# Titan_Balancer.net
KiCad netlist of a schematic drawn in EAGLE
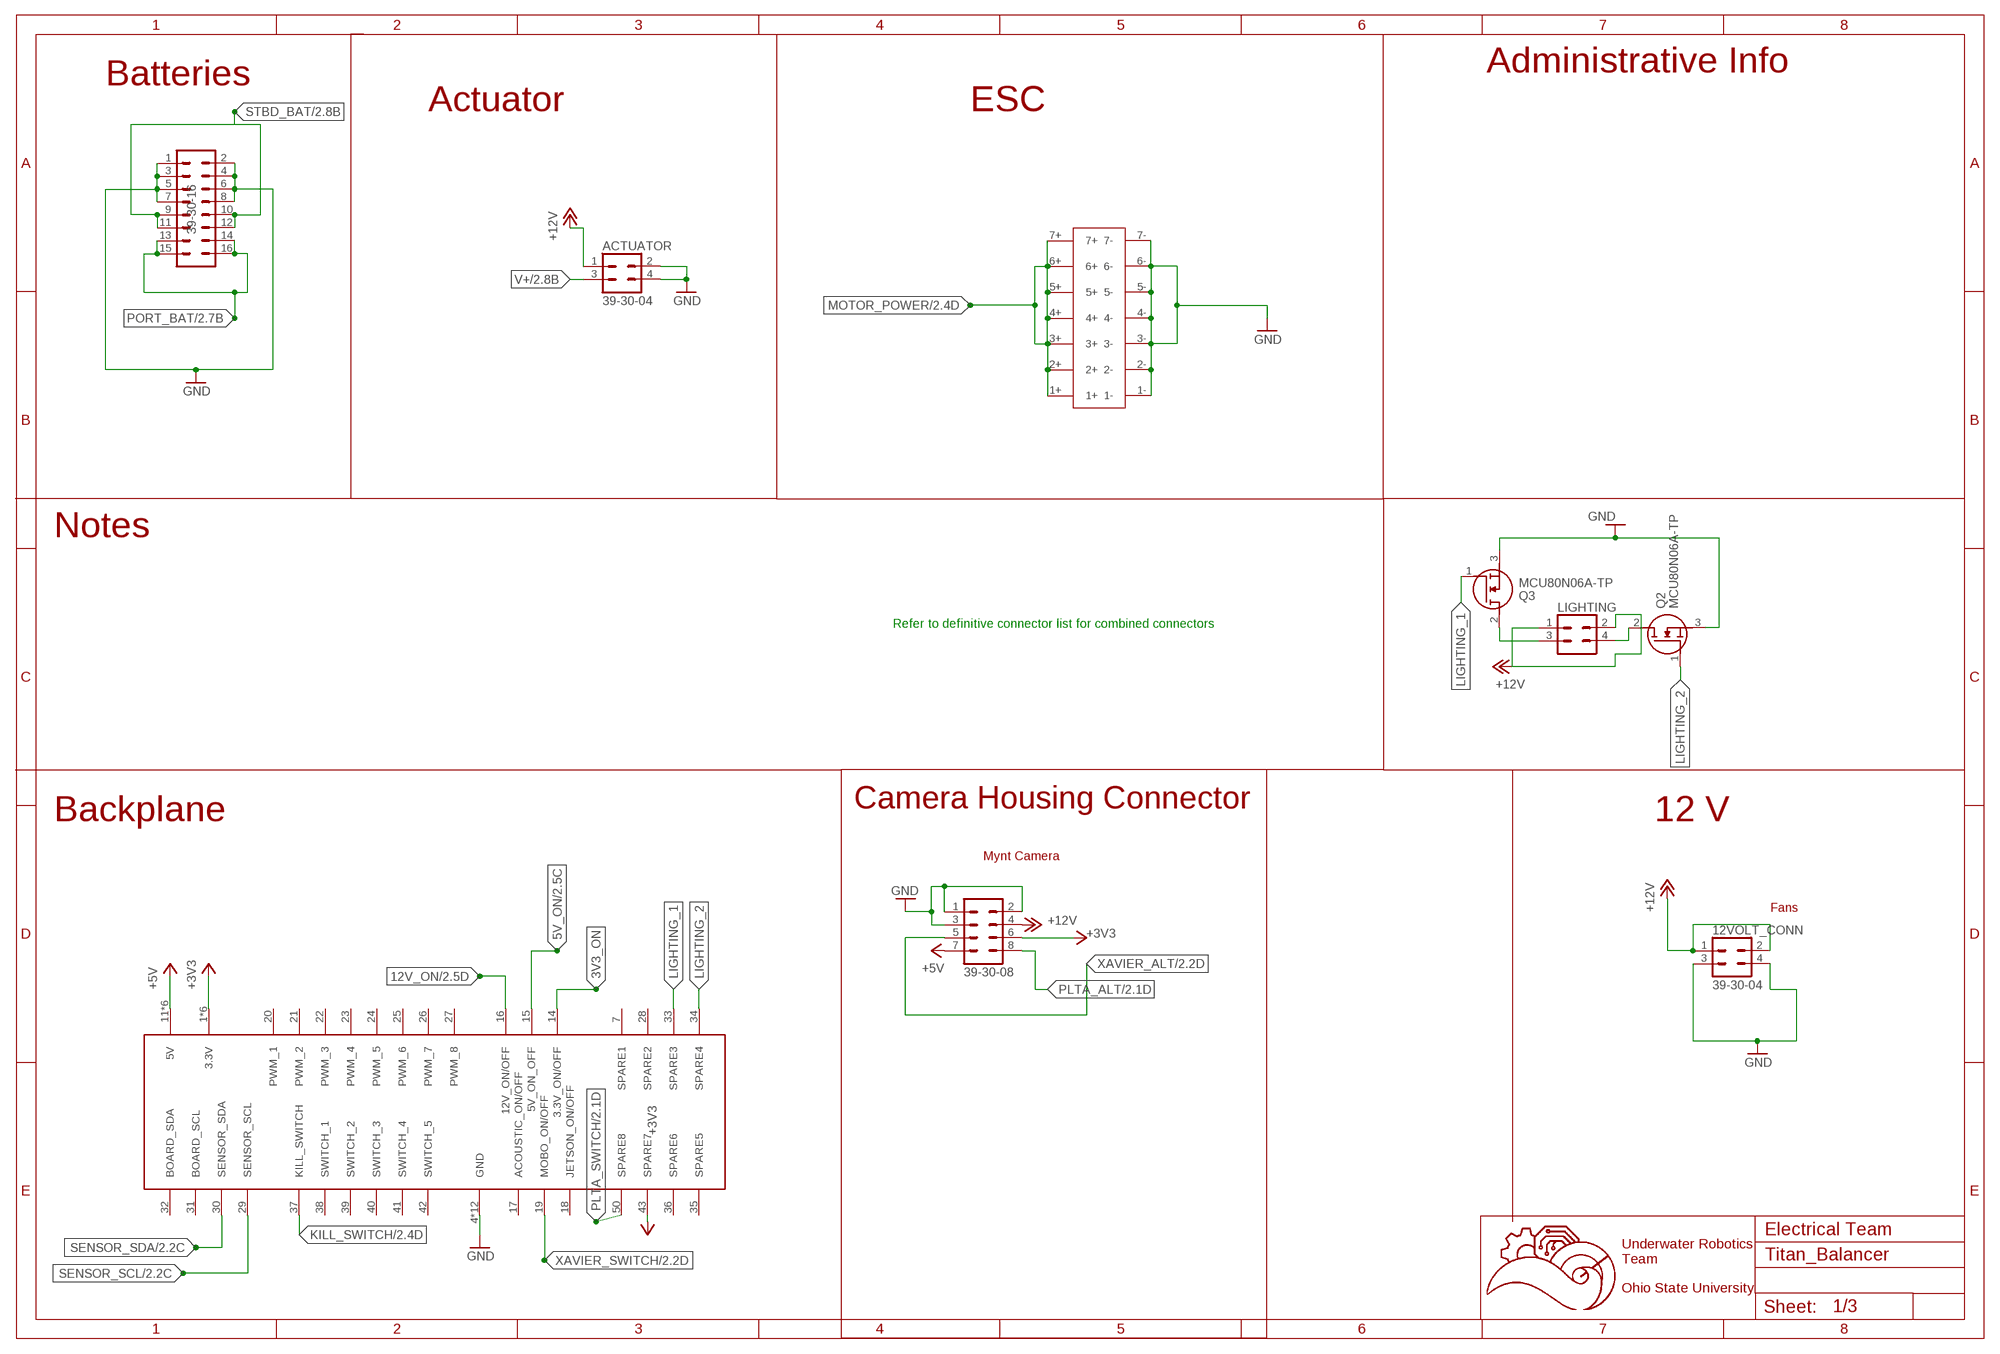
[diagram p0: schematic, sheet 1]
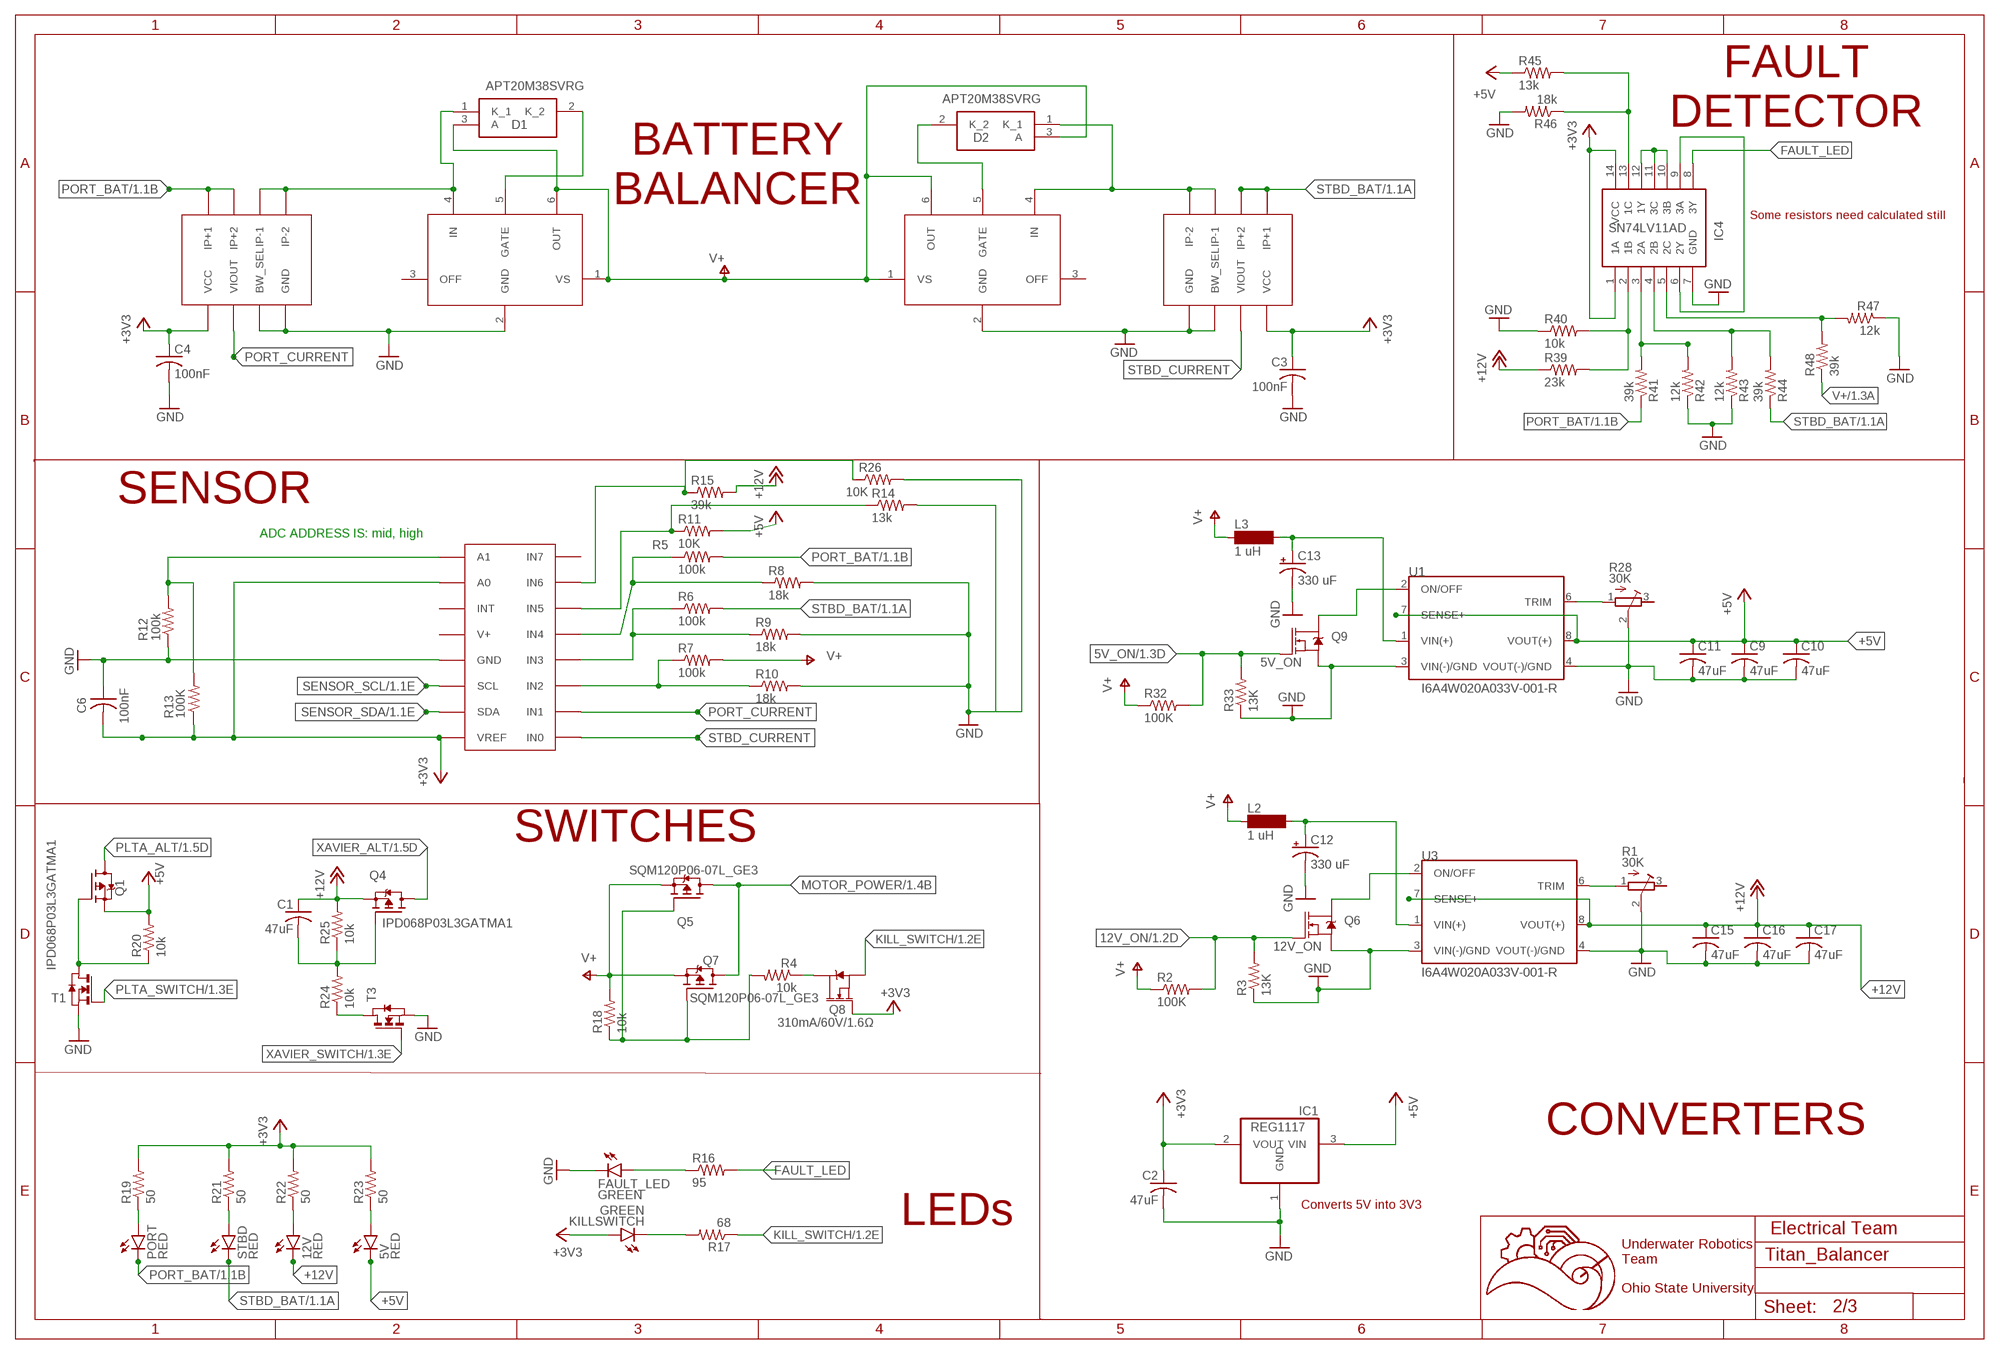
[diagram p1: schematic, sheet 2]
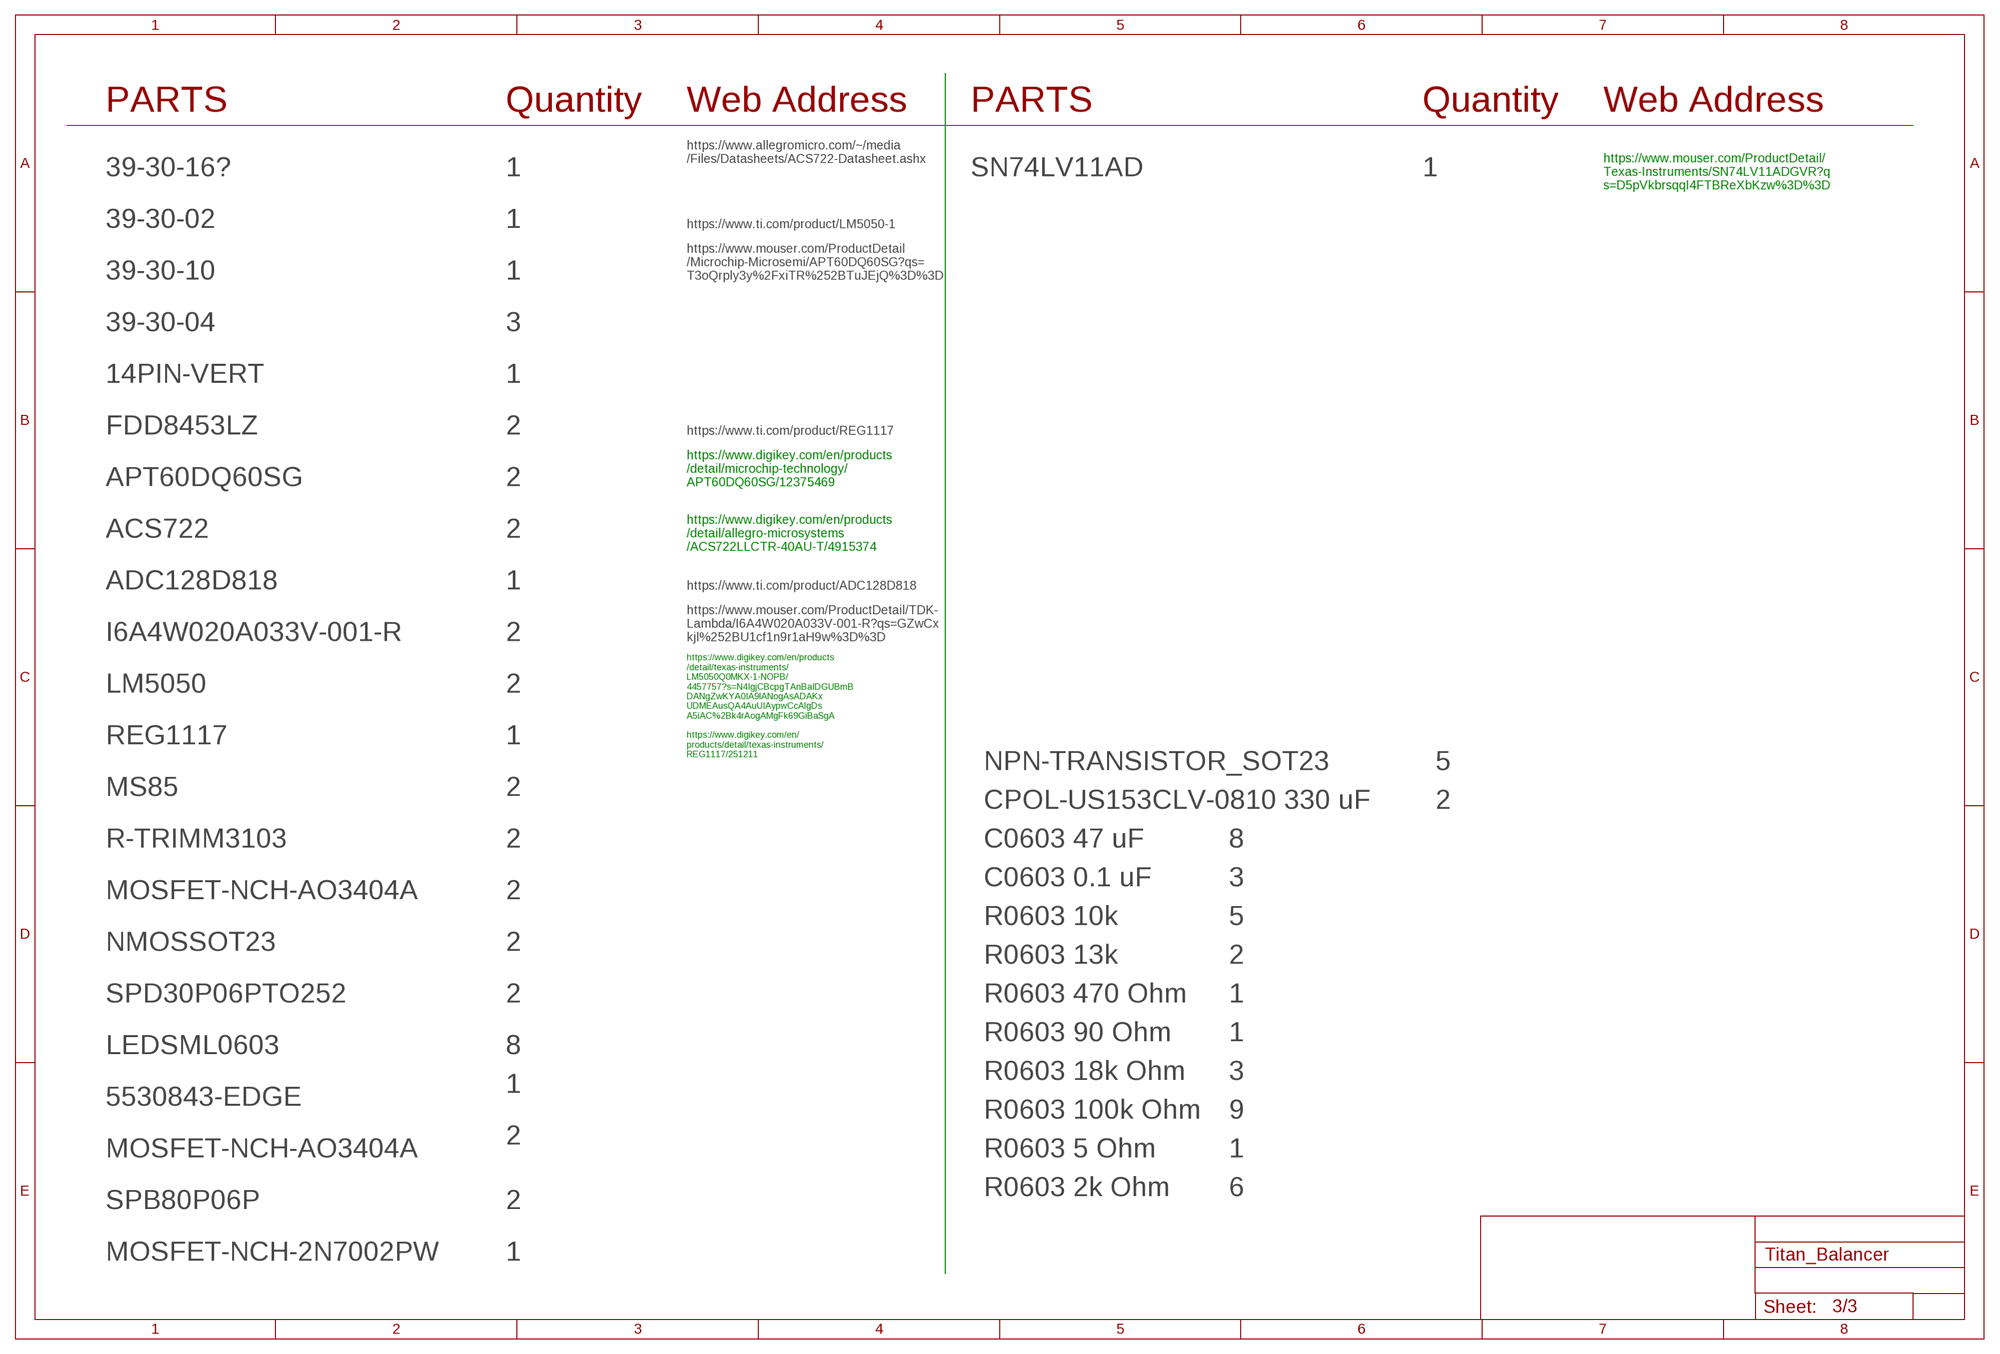
[diagram p2: schematic, sheet 3]

(export (version "E")
  (design (tool "Eeschema 10.0.6"))
  (components
    (comp (ref "12VOLT_CONN")
      (value "39-30-04")
      (footprint "eagle-import:39-30-_04_")
      (libsource (lib "eagle-import") (part "39-30-?04?"))
    )
    (comp (ref "ACTUATOR")
      (value "39-30-04")
      (footprint "eagle-import:39-30-_04_")
      (libsource (lib "eagle-import") (part "39-30-?04?"))
    )
    (comp (ref "BATTERYCONNECTOR")
      (value "39-30-16")
      (footprint "eagle-import:39-30-_16_")
      (libsource (lib "eagle-import") (part "39-30-?16?"))
    )
    (comp (ref "ESC_CONN")
      (value "14PIN-VERT")
      (footprint "eagle-import:14PIN_VERT")
      (libsource (lib "eagle-import") (part "14PIN-VERT"))
    )
    (comp (ref "LIGHTING")
      (value "39-30-04")
      (footprint "eagle-import:39-30-_04_")
      (libsource (lib "eagle-import") (part "39-30-?04?"))
    )
    (comp (ref "MYNT_XAVIER_PLTA")
      (value "39-30-08")
      (footprint "eagle-import:39-30-_08_")
      (libsource (lib "eagle-import") (part "39-30-?08?"))
    )
    (comp (ref "Q2")
      (value "MCU80N06A-TP")
      (footprint "eagle-import:FDD8453LZ")
      (fields
        (field (name "MANUFACTURER_PART_NUMBER") "FDD8453LZ")
        (field (name "MOUSER_PART_NUMBER") "512-FDD8453LZ")
      )
      (libsource (lib "eagle-import") (part "FDD8453LZ"))
    )
    (comp (ref "Q3")
      (value "MCU80N06A-TP")
      (footprint "eagle-import:FDD8453LZ")
      (fields
        (field (name "MANUFACTURER_PART_NUMBER") "FDD8453LZ")
        (field (name "MOUSER_PART_NUMBER") "512-FDD8453LZ")
      )
      (libsource (lib "eagle-import") (part "FDD8453LZ"))
    )
    (comp (ref "U$1")
      (value "5530843-EDGE")
      (footprint "eagle-import:5530843-6-BOARDFINGERS")
      (libsource (lib "eagle-import") (part "5530843-EDGE"))
    )
    (comp (ref "5V")
      (value "RED")
      (footprint "eagle-import:SML0603")
      (libsource (lib "eagle-import") (part "LEDSML0603"))
    )
    (comp (ref "12V")
      (value "RED")
      (footprint "eagle-import:SML0603")
      (libsource (lib "eagle-import") (part "LEDSML0603"))
    )
    (comp (ref "C1")
      (value "47uF")
      (footprint "eagle-import:C0603")
      (libsource (lib "eagle-import") (part "C-USC0603"))
    )
    (comp (ref "C2")
      (value "47uF")
      (footprint "eagle-import:C0603")
      (libsource (lib "eagle-import") (part "C-USC0603"))
    )
    (comp (ref "C3")
      (value "100nF")
      (footprint "eagle-import:C0603")
      (libsource (lib "eagle-import") (part "C-USC0603"))
    )
    (comp (ref "C4")
      (value "100nF")
      (footprint "eagle-import:C0603")
      (libsource (lib "eagle-import") (part "C-USC0603"))
    )
    (comp (ref "C6")
      (value "100nF")
      (footprint "eagle-import:C0603")
      (libsource (lib "eagle-import") (part "C-USC0603"))
    )
    (comp (ref "C9")
      (value "47uF")
      (footprint "eagle-import:C0603")
      (libsource (lib "eagle-import") (part "C-USC0603"))
    )
    (comp (ref "C10")
      (value "47uF")
      (footprint "eagle-import:C0603")
      (libsource (lib "eagle-import") (part "C-USC0603"))
    )
    (comp (ref "C11")
      (value "47uF")
      (footprint "eagle-import:C0603")
      (libsource (lib "eagle-import") (part "C-USC0603"))
    )
    (comp (ref "C12")
      (value "330 uF")
      (footprint "eagle-import:153CLV-0810")
      (libsource (lib "eagle-import") (part "CPOL-US153CLV-0810"))
    )
    (comp (ref "C13")
      (value "330 uF")
      (footprint "eagle-import:153CLV-0810")
      (libsource (lib "eagle-import") (part "CPOL-US153CLV-0810"))
    )
    (comp (ref "C15")
      (value "47uF")
      (footprint "eagle-import:C0603")
      (libsource (lib "eagle-import") (part "C-USC0603"))
    )
    (comp (ref "C16")
      (value "47uF")
      (footprint "eagle-import:C0603")
      (libsource (lib "eagle-import") (part "C-USC0603"))
    )
    (comp (ref "C17")
      (value "47uF")
      (footprint "eagle-import:C0603")
      (libsource (lib "eagle-import") (part "C-USC0603"))
    )
    (comp (ref "D1")
      (value "APT20M38SVRG")
      (footprint "eagle-import:APT60DQ60SG")
      (fields
        (field (name "ARROW_PART_NUMBER") "APT60DQ60SG")
        (field (name "MOUSER_PART_NUMBER") "494-APT60DQ60SG")
      )
      (libsource (lib "eagle-import") (part "APT60DQ60SG"))
    )
    (comp (ref "D2")
      (value "APT20M38SVRG")
      (footprint "eagle-import:APT60DQ60SG")
      (fields
        (field (name "ARROW_PART_NUMBER") "APT60DQ60SG")
        (field (name "MOUSER_PART_NUMBER") "494-APT60DQ60SG")
      )
      (libsource (lib "eagle-import") (part "APT60DQ60SG"))
    )
    (comp (ref "FAULT_LED")
      (value "GREEN")
      (footprint "eagle-import:SML0603")
      (libsource (lib "eagle-import") (part "LEDSML0603"))
    )
    (comp (ref "IC1")
      (value "REG1117")
      (footprint "eagle-import:SOT223")
      (libsource (lib "eagle-import") (part "REG1117"))
    )
    (comp (ref "IC4")
      (value "SN74LV11AD")
      (footprint "eagle-import:SOIC127P600X175-14N")
      (fields (field (name "MOUSER_PART_NUMBER") "595-SN74LV11AD"))
      (libsource (lib "eagle-import") (part "SN74LV11AD"))
    )
    (comp (ref "KILLSWITCH")
      (value "GREEN")
      (footprint "eagle-import:SML0603")
      (libsource (lib "eagle-import") (part "LEDSML0603"))
    )
    (comp (ref "L2")
      (value "1 uH")
      (footprint "eagle-import:MS85")
      (libsource (lib "eagle-import") (part "MS85"))
    )
    (comp (ref "L3")
      (value "1 uH")
      (footprint "eagle-import:MS85")
      (libsource (lib "eagle-import") (part "MS85"))
    )
    (comp (ref "PORT")
      (value "RED")
      (footprint "eagle-import:SML0603")
      (libsource (lib "eagle-import") (part "LEDSML0603"))
    )
    (comp (ref "Q1")
      (value "IPD068P03L3GATMA1")
      (footprint "eagle-import:TO252")
      (libsource (lib "eagle-import") (part "SPD30P06PTO252"))
    )
    (comp (ref "Q4")
      (value "IPD068P03L3GATMA1")
      (footprint "eagle-import:TO252")
      (libsource (lib "eagle-import") (part "SPD30P06PTO252"))
    )
    (comp (ref "Q5")
      (value "SQM120P06-07L_GE3")
      (footprint "eagle-import:TO263")
      (libsource (lib "eagle-import") (part "SPB80P06P"))
    )
    (comp (ref "Q6")
      (value "MOSFET-NCH-AO3404A")
      (footprint "eagle-import:SOT23-3")
      (libsource (lib "eagle-import") (part "MOSFET-NCH-AO3404A"))
    )
    (comp (ref "Q7")
      (value "SQM120P06-07L_GE3")
      (footprint "eagle-import:TO263")
      (libsource (lib "eagle-import") (part "SPB80P06P"))
    )
    (comp (ref "Q8")
      (value "310mA/60V/1.6Ω")
      (footprint "eagle-import:SOT323")
      (libsource (lib "eagle-import") (part "SparkFun-DiscreteSemi_514_MOSFET-NCH-2N7002PW"))
    )
    (comp (ref "Q9")
      (value "MOSFET-NCH-AO3404A")
      (footprint "eagle-import:SOT23-3")
      (libsource (lib "eagle-import") (part "MOSFET-NCH-AO3404A"))
    )
    (comp (ref "R1")
      (value "30K")
      (footprint "eagle-import:RTRIM3103")
      (libsource (lib "eagle-import") (part "R-TRIMM3103"))
    )
    (comp (ref "R2")
      (value "100K")
      (footprint "eagle-import:R0603")
      (libsource (lib "eagle-import") (part "R-US_R0603"))
    )
    (comp (ref "R3")
      (value "13K")
      (footprint "eagle-import:R0603")
      (libsource (lib "eagle-import") (part "R-US_R0603"))
    )
    (comp (ref "R4")
      (value "10k")
      (footprint "eagle-import:R0603")
      (libsource (lib "eagle-import") (part "R-US_R0603"))
    )
    (comp (ref "R5")
      (value "100k")
      (footprint "eagle-import:R0603")
      (libsource (lib "eagle-import") (part "R-US_R0603"))
    )
    (comp (ref "R6")
      (value "100k")
      (footprint "eagle-import:R0603")
      (libsource (lib "eagle-import") (part "R-US_R0603"))
    )
    (comp (ref "R7")
      (value "100k")
      (footprint "eagle-import:R0603")
      (libsource (lib "eagle-import") (part "R-US_R0603"))
    )
    (comp (ref "R8")
      (value "18k")
      (footprint "eagle-import:R0603")
      (libsource (lib "eagle-import") (part "R-US_R0603"))
    )
    (comp (ref "R9")
      (value "18k")
      (footprint "eagle-import:R0603")
      (libsource (lib "eagle-import") (part "R-US_R0603"))
    )
    (comp (ref "R10")
      (value "18k")
      (footprint "eagle-import:R0603")
      (libsource (lib "eagle-import") (part "R-US_R0603"))
    )
    (comp (ref "R11")
      (value "10K")
      (footprint "eagle-import:R0603")
      (libsource (lib "eagle-import") (part "R-US_R0603"))
    )
    (comp (ref "R12")
      (value "100k")
      (footprint "eagle-import:R0603")
      (libsource (lib "eagle-import") (part "R-US_R0603"))
    )
    (comp (ref "R13")
      (value "100K")
      (footprint "eagle-import:R0603")
      (libsource (lib "eagle-import") (part "R-US_R0603"))
    )
    (comp (ref "R14")
      (value "13k")
      (footprint "eagle-import:R0603")
      (libsource (lib "eagle-import") (part "R-US_R0603"))
    )
    (comp (ref "R15")
      (value "39k")
      (footprint "eagle-import:R0603")
      (libsource (lib "eagle-import") (part "R-US_R0603"))
    )
    (comp (ref "R16")
      (value "95")
      (footprint "eagle-import:R0603")
      (libsource (lib "eagle-import") (part "R-US_R0603"))
    )
    (comp (ref "R17")
      (value "68")
      (footprint "eagle-import:R0603")
      (libsource (lib "eagle-import") (part "R-US_R0603"))
    )
    (comp (ref "R18")
      (value "10k")
      (footprint "eagle-import:R0603")
      (libsource (lib "eagle-import") (part "R-US_R0603"))
    )
    (comp (ref "R19")
      (value "50")
      (footprint "eagle-import:R0603")
      (libsource (lib "eagle-import") (part "R-US_R0603"))
    )
    (comp (ref "R20")
      (value "10k")
      (footprint "eagle-import:R0603")
      (libsource (lib "eagle-import") (part "R-US_R0603"))
    )
    (comp (ref "R21")
      (value "50")
      (footprint "eagle-import:R0603")
      (libsource (lib "eagle-import") (part "R-US_R0603"))
    )
    (comp (ref "R22")
      (value "50")
      (footprint "eagle-import:R0603")
      (libsource (lib "eagle-import") (part "R-US_R0603"))
    )
    (comp (ref "R23")
      (value "50")
      (footprint "eagle-import:R0603")
      (libsource (lib "eagle-import") (part "R-US_R0603"))
    )
    (comp (ref "R24")
      (value "10k")
      (footprint "eagle-import:R0603")
      (libsource (lib "eagle-import") (part "R-US_R0603"))
    )
    (comp (ref "R25")
      (value "10k")
      (footprint "eagle-import:R0603")
      (libsource (lib "eagle-import") (part "R-US_R0603"))
    )
    (comp (ref "R26")
      (value "10K")
      (footprint "eagle-import:R0603")
      (libsource (lib "eagle-import") (part "R-US_R0603"))
    )
    (comp (ref "R28")
      (value "30K")
      (footprint "eagle-import:RTRIM3103")
      (libsource (lib "eagle-import") (part "R-TRIMM3103"))
    )
    (comp (ref "R32")
      (value "100K")
      (footprint "eagle-import:R0603")
      (libsource (lib "eagle-import") (part "R-US_R0603"))
    )
    (comp (ref "R33")
      (value "13K")
      (footprint "eagle-import:R0603")
      (libsource (lib "eagle-import") (part "R-US_R0603"))
    )
    (comp (ref "R39")
      (value "23k")
      (footprint "eagle-import:R0603")
      (libsource (lib "eagle-import") (part "R-US_R0603"))
    )
    (comp (ref "R40")
      (value "10k")
      (footprint "eagle-import:R0603")
      (libsource (lib "eagle-import") (part "R-US_R0603"))
    )
    (comp (ref "R41")
      (value "39k")
      (footprint "eagle-import:R0603")
      (libsource (lib "eagle-import") (part "R-US_R0603"))
    )
    (comp (ref "R42")
      (value "12k")
      (footprint "eagle-import:R0603")
      (libsource (lib "eagle-import") (part "R-US_R0603"))
    )
    (comp (ref "R43")
      (value "12k")
      (footprint "eagle-import:R0603")
      (libsource (lib "eagle-import") (part "R-US_R0603"))
    )
    (comp (ref "R44")
      (value "39k")
      (footprint "eagle-import:R0603")
      (libsource (lib "eagle-import") (part "R-US_R0603"))
    )
    (comp (ref "R45")
      (value "13k")
      (footprint "eagle-import:R0603")
      (libsource (lib "eagle-import") (part "R-US_R0603"))
    )
    (comp (ref "R46")
      (value "18k")
      (footprint "eagle-import:R0603")
      (libsource (lib "eagle-import") (part "R-US_R0603"))
    )
    (comp (ref "R47")
      (value "12k")
      (footprint "eagle-import:R0603")
      (libsource (lib "eagle-import") (part "R-US_R0603"))
    )
    (comp (ref "R48")
      (value "39k")
      (footprint "eagle-import:R0603")
      (libsource (lib "eagle-import") (part "R-US_R0603"))
    )
    (comp (ref "STBD")
      (value "RED")
      (footprint "eagle-import:SML0603")
      (libsource (lib "eagle-import") (part "LEDSML0603"))
    )
    (comp (ref "T1")
      (value "NMOSSOT23")
      (footprint "eagle-import:SOT-23")
      (libsource (lib "eagle-import") (part "NMOSSOT23"))
    )
    (comp (ref "T3")
      (value "NMOSSOT23")
      (footprint "eagle-import:SOT-23")
      (libsource (lib "eagle-import") (part "NMOSSOT23"))
    )
    (comp (ref "U$5")
      (value "LM5050")
      (footprint "eagle-import:LM5050")
      (libsource (lib "eagle-import") (part "LM5050"))
    )
    (comp (ref "U$6")
      (value "LM5050")
      (footprint "eagle-import:LM5050")
      (libsource (lib "eagle-import") (part "LM5050"))
    )
    (comp (ref "U$7")
      (value "ACS722")
      (footprint "eagle-import:SOIC-8")
      (libsource (lib "eagle-import") (part "ACS722"))
    )
    (comp (ref "U$8")
      (value "ACS722")
      (footprint "eagle-import:SOIC-8")
      (libsource (lib "eagle-import") (part "ACS722"))
    )
    (comp (ref "U$9")
      (value "ADC128D818")
      (footprint "eagle-import:TSSOP-16")
      (libsource (lib "eagle-import") (part "ADC128D818"))
    )
    (comp (ref "U1")
      (value "I6A4W020A033V-001-R")
      (footprint "eagle-import:TDK-LAMBDA_I6A4W020A033V-001-R")
      (fields (field (name "DIGI-KEY_PART_NUMBER") "285-2503-ND") (field (name "MF") "TDK-Lambda Americas"))
      (libsource (lib "eagle-import") (part "I6A4W020A033V-001-R"))
    )
    (comp (ref "U3")
      (value "I6A4W020A033V-001-R")
      (footprint "eagle-import:TDK-LAMBDA_I6A4W020A033V-001-R")
      (fields (field (name "DIGI-KEY_PART_NUMBER") "285-2503-ND") (field (name "MF") "TDK-Lambda Americas"))
      (libsource (lib "eagle-import") (part "I6A4W020A033V-001-R"))
    )
  )
  (nets
    (net (code "1") (name "+3V3") (class "Default")
      (node (ref "C2") (pin "1") (pinfunction "1_1") (pintype "passive"))
      (node (ref "C3") (pin "1") (pinfunction "1_1") (pintype "passive"))
      (node (ref "C4") (pin "1") (pinfunction "1_1") (pintype "passive"))
      (node (ref "C6") (pin "2") (pinfunction "2_2") (pintype "passive"))
      (node (ref "IC1") (pin "2") (pinfunction "VOUT_2") (pintype "output"))
      (node (ref "IC4") (pin "1") (pinfunction "1A_1") (pintype "input"))
      (node (ref "IC4") (pin "14") (pinfunction "VCC_14") (pintype "power_in"))
      (node (ref "KILLSWITCH") (pin "A") (pinfunction "A_A") (pintype "passive"))
      (node (ref "MYNT_XAVIER_PLTA") (pin "6") (pinfunction "6_6") (pintype "passive"))
      (node (ref "Q8") (pin "1") (pinfunction "G_1") (pintype "bidirectional"))
      (node (ref "R13") (pin "1") (pinfunction "1_1") (pintype "passive"))
      (node (ref "R19") (pin "2") (pinfunction "2_2") (pintype "passive"))
      (node (ref "R21") (pin "2") (pinfunction "2_2") (pintype "passive"))
      (node (ref "R22") (pin "2") (pinfunction "2_2") (pintype "passive"))
      (node (ref "R23") (pin "2") (pinfunction "2_2") (pintype "passive"))
      (node (ref "U$1") (pin "1") (pinfunction "3.3V_1") (pintype "bidirectional"))
      (node (ref "U$1") (pin "2") (pinfunction "3.3V_2") (pintype "bidirectional"))
      (node (ref "U$1") (pin "3") (pinfunction "3.3V_3") (pintype "bidirectional"))
      (node (ref "U$1") (pin "43") (pinfunction "SPARE7_43") (pintype "bidirectional"))
      (node (ref "U$1") (pin "54") (pinfunction "3.3V_54") (pintype "bidirectional"))
      (node (ref "U$1") (pin "55") (pinfunction "3.3V_55") (pintype "bidirectional"))
      (node (ref "U$1") (pin "56") (pinfunction "3.3V_56") (pintype "bidirectional"))
      (node (ref "U$7") (pin "VCC") (pinfunction "VCC_VCC") (pintype "bidirectional"))
      (node (ref "U$8") (pin "VCC") (pinfunction "VCC_VCC") (pintype "bidirectional"))
      (node (ref "U$9") (pin "A0") (pinfunction "A0_A0") (pintype "bidirectional"))
      (node (ref "U$9") (pin "VREF") (pinfunction "VREF_VREF") (pintype "bidirectional"))
    )
    (net (code "2") (name "+5V") (class "Default")
      (node (ref "5V") (pin "C") (pinfunction "C_C") (pintype "passive"))
      (node (ref "C10") (pin "1") (pinfunction "1_1") (pintype "passive"))
      (node (ref "C11") (pin "1") (pinfunction "1_1") (pintype "passive"))
      (node (ref "C9") (pin "1") (pinfunction "1_1") (pintype "passive"))
      (node (ref "IC1") (pin "3") (pinfunction "VIN_3") (pintype "input"))
      (node (ref "MYNT_XAVIER_PLTA") (pin "7") (pinfunction "7_7") (pintype "passive"))
      (node (ref "Q1") (pin "2") (pinfunction "S_2") (pintype "passive"))
      (node (ref "R11") (pin "2") (pinfunction "2_2") (pintype "passive"))
      (node (ref "R20") (pin "2") (pinfunction "2_2") (pintype "passive"))
      (node (ref "R45") (pin "1") (pinfunction "1_1") (pintype "passive"))
      (node (ref "U$1") (pin "11") (pinfunction "5V_11") (pintype "bidirectional"))
      (node (ref "U$1") (pin "12") (pinfunction "5V_12") (pintype "bidirectional"))
      (node (ref "U$1") (pin "13") (pinfunction "5V_13") (pintype "bidirectional"))
      (node (ref "U$1") (pin "44") (pinfunction "5V_44") (pintype "bidirectional"))
      (node (ref "U$1") (pin "45") (pinfunction "5V_45") (pintype "bidirectional"))
      (node (ref "U$1") (pin "46") (pinfunction "5V_46") (pintype "bidirectional"))
      (node (ref "U1") (pin "7") (pinfunction "SENSE+_7") (pintype "input"))
      (node (ref "U1") (pin "8") (pinfunction "VOUT(+)_8") (pintype "output"))
    )
    (net (code "3") (name "+12V") (class "Default")
      (node (ref "12V") (pin "C") (pinfunction "C_C") (pintype "passive"))
      (node (ref "12VOLT_CONN") (pin "1") (pinfunction "1_1") (pintype "passive"))
      (node (ref "12VOLT_CONN") (pin "2") (pinfunction "2_2") (pintype "passive"))
      (node (ref "ACTUATOR") (pin "1") (pinfunction "1_1") (pintype "passive"))
      (node (ref "C1") (pin "1") (pinfunction "1_1") (pintype "passive"))
      (node (ref "C15") (pin "1") (pinfunction "1_1") (pintype "passive"))
      (node (ref "C16") (pin "1") (pinfunction "1_1") (pintype "passive"))
      (node (ref "C17") (pin "1") (pinfunction "1_1") (pintype "passive"))
      (node (ref "LIGHTING") (pin "1") (pinfunction "1_1") (pintype "passive"))
      (node (ref "LIGHTING") (pin "2") (pinfunction "2_2") (pintype "passive"))
      (node (ref "MYNT_XAVIER_PLTA") (pin "4") (pinfunction "4_4") (pintype "passive"))
      (node (ref "Q4") (pin "2") (pinfunction "S_2") (pintype "passive"))
      (node (ref "R15") (pin "2") (pinfunction "2_2") (pintype "passive"))
      (node (ref "R25") (pin "2") (pinfunction "2_2") (pintype "passive"))
      (node (ref "R39") (pin "1") (pinfunction "1_1") (pintype "passive"))
      (node (ref "U3") (pin "7") (pinfunction "SENSE+_7") (pintype "input"))
      (node (ref "U3") (pin "8") (pinfunction "VOUT(+)_8") (pintype "output"))
    )
    (net (code "4") (name "3V3_ON") (class "Default")
      (node (ref "U$1") (pin "14") (pinfunction "3.3V_ON/OFF_14") (pintype "bidirectional"))
    )
    (net (code "5") (name "5V_ON") (class "Default")
      (node (ref "Q9") (pin "1") (pinfunction "G_1") (pintype "bidirectional"))
      (node (ref "R32") (pin "2") (pinfunction "2_2") (pintype "passive"))
      (node (ref "R33") (pin "2") (pinfunction "2_2") (pintype "passive"))
      (node (ref "U$1") (pin "15") (pinfunction "5V_ON_OFF_15") (pintype "bidirectional"))
    )
    (net (code "6") (name "12V_ON") (class "Default")
      (node (ref "Q6") (pin "1") (pinfunction "G_1") (pintype "bidirectional"))
      (node (ref "R2") (pin "2") (pinfunction "2_2") (pintype "passive"))
      (node (ref "R3") (pin "2") (pinfunction "2_2") (pintype "passive"))
      (node (ref "U$1") (pin "16") (pinfunction "12V_ON/OFF_16") (pintype "bidirectional"))
    )
    (net (code "7") (name "FAULT_LED") (class "Default")
      (node (ref "IC4") (pin "8") (pinfunction "3Y_8") (pintype "output"))
      (node (ref "R16") (pin "2") (pinfunction "2_2") (pintype "passive"))
    )
    (net (code "8") (name "GND") (class "Default")
      (node (ref "12VOLT_CONN") (pin "3") (pinfunction "3_3") (pintype "passive"))
      (node (ref "12VOLT_CONN") (pin "4") (pinfunction "4_4") (pintype "passive"))
      (node (ref "ACTUATOR") (pin "2") (pinfunction "2_2") (pintype "passive"))
      (node (ref "ACTUATOR") (pin "4") (pinfunction "4_4") (pintype "passive"))
      (node (ref "BATTERYCONNECTOR") (pin "1") (pinfunction "1_1") (pintype "passive"))
      (node (ref "BATTERYCONNECTOR") (pin "2") (pinfunction "2_2") (pintype "passive"))
      (node (ref "BATTERYCONNECTOR") (pin "3") (pinfunction "3_3") (pintype "passive"))
      (node (ref "BATTERYCONNECTOR") (pin "4") (pinfunction "4_4") (pintype "passive"))
      (node (ref "BATTERYCONNECTOR") (pin "5") (pinfunction "5_5") (pintype "passive"))
      (node (ref "BATTERYCONNECTOR") (pin "6") (pinfunction "6_6") (pintype "passive"))
      (node (ref "BATTERYCONNECTOR") (pin "7") (pinfunction "7_7") (pintype "passive"))
      (node (ref "BATTERYCONNECTOR") (pin "8") (pinfunction "8_8") (pintype "passive"))
      (node (ref "C10") (pin "2") (pinfunction "2_2") (pintype "passive"))
      (node (ref "C11") (pin "2") (pinfunction "2_2") (pintype "passive"))
      (node (ref "C12") (pin "-") (pinfunction "-_-") (pintype "passive"))
      (node (ref "C13") (pin "-") (pinfunction "-_-") (pintype "passive"))
      (node (ref "C15") (pin "2") (pinfunction "2_2") (pintype "passive"))
      (node (ref "C16") (pin "2") (pinfunction "2_2") (pintype "passive"))
      (node (ref "C17") (pin "2") (pinfunction "2_2") (pintype "passive"))
      (node (ref "C2") (pin "2") (pinfunction "2_2") (pintype "passive"))
      (node (ref "C3") (pin "2") (pinfunction "2_2") (pintype "passive"))
      (node (ref "C4") (pin "2") (pinfunction "2_2") (pintype "passive"))
      (node (ref "C6") (pin "1") (pinfunction "1_1") (pintype "passive"))
      (node (ref "C9") (pin "2") (pinfunction "2_2") (pintype "passive"))
      (node (ref "ESC_CONN") (pin "1-") (pinfunction "1-_1-") (pintype "bidirectional"))
      (node (ref "ESC_CONN") (pin "2-") (pinfunction "2-_2-") (pintype "bidirectional"))
      (node (ref "ESC_CONN") (pin "3-") (pinfunction "3-_3-") (pintype "bidirectional"))
      (node (ref "ESC_CONN") (pin "4-") (pinfunction "4-_4-") (pintype "bidirectional"))
      (node (ref "ESC_CONN") (pin "5-") (pinfunction "5-_5-") (pintype "bidirectional"))
      (node (ref "ESC_CONN") (pin "6-") (pinfunction "6-_6-") (pintype "bidirectional"))
      (node (ref "ESC_CONN") (pin "7-") (pinfunction "7-_7-") (pintype "bidirectional"))
      (node (ref "FAULT_LED") (pin "C") (pinfunction "C_C") (pintype "passive"))
      (node (ref "IC1") (pin "1") (pinfunction "GND_1") (pintype "power_in"))
      (node (ref "IC4") (pin "7") (pinfunction "GND_7") (pintype "power_in"))
      (node (ref "MYNT_XAVIER_PLTA") (pin "1") (pinfunction "1_1") (pintype "passive"))
      (node (ref "MYNT_XAVIER_PLTA") (pin "2") (pinfunction "2_2") (pintype "passive"))
      (node (ref "MYNT_XAVIER_PLTA") (pin "3") (pinfunction "3_3") (pintype "passive"))
      (node (ref "Q2") (pin "3") (pinfunction "S_3") (pintype "bidirectional"))
      (node (ref "Q3") (pin "3") (pinfunction "S_3") (pintype "bidirectional"))
      (node (ref "Q6") (pin "2") (pinfunction "S_2") (pintype "bidirectional"))
      (node (ref "Q9") (pin "2") (pinfunction "S_2") (pintype "bidirectional"))
      (node (ref "R1") (pin "2") (pinfunction "S_2") (pintype "passive"))
      (node (ref "R10") (pin "2") (pinfunction "2_2") (pintype "passive"))
      (node (ref "R12") (pin "1") (pinfunction "1_1") (pintype "passive"))
      (node (ref "R14") (pin "2") (pinfunction "2_2") (pintype "passive"))
      (node (ref "R26") (pin "2") (pinfunction "2_2") (pintype "passive"))
      (node (ref "R28") (pin "2") (pinfunction "S_2") (pintype "passive"))
      (node (ref "R3") (pin "1") (pinfunction "1_1") (pintype "passive"))
      (node (ref "R33") (pin "1") (pinfunction "1_1") (pintype "passive"))
      (node (ref "R40") (pin "1") (pinfunction "1_1") (pintype "passive"))
      (node (ref "R42") (pin "1") (pinfunction "1_1") (pintype "passive"))
      (node (ref "R43") (pin "1") (pinfunction "1_1") (pintype "passive"))
      (node (ref "R46") (pin "2") (pinfunction "2_2") (pintype "passive"))
      (node (ref "R47") (pin "1") (pinfunction "1_1") (pintype "passive"))
      (node (ref "R8") (pin "2") (pinfunction "2_2") (pintype "passive"))
      (node (ref "R9") (pin "2") (pinfunction "2_2") (pintype "passive"))
      (node (ref "T1") (pin "2") (pinfunction "S_2") (pintype "passive"))
      (node (ref "T3") (pin "2") (pinfunction "S_2") (pintype "passive"))
      (node (ref "U$1") (pin "10") (pinfunction "GND_10") (pintype "bidirectional"))
      (node (ref "U$1") (pin "4") (pinfunction "GND_4") (pintype "bidirectional"))
      (node (ref "U$1") (pin "47") (pinfunction "GND_47") (pintype "bidirectional"))
      (node (ref "U$1") (pin "48") (pinfunction "GND_48") (pintype "bidirectional"))
      (node (ref "U$1") (pin "49") (pinfunction "GND_49") (pintype "bidirectional"))
      (node (ref "U$1") (pin "5") (pinfunction "GND_5") (pintype "bidirectional"))
      (node (ref "U$1") (pin "51") (pinfunction "GND_51") (pintype "bidirectional"))
      (node (ref "U$1") (pin "52") (pinfunction "GND_52") (pintype "bidirectional"))
      (node (ref "U$1") (pin "53") (pinfunction "GND_53") (pintype "bidirectional"))
      (node (ref "U$1") (pin "6") (pinfunction "GND_6") (pintype "bidirectional"))
      (node (ref "U$1") (pin "8") (pinfunction "GND_8") (pintype "bidirectional"))
      (node (ref "U$1") (pin "9") (pinfunction "GND_9") (pintype "bidirectional"))
      (node (ref "U$5") (pin "2") (pinfunction "GND_2") (pintype "bidirectional"))
      (node (ref "U$6") (pin "2") (pinfunction "GND_2") (pintype "bidirectional"))
      (node (ref "U$7") (pin "BW_SEL") (pinfunction "BW_SEL_BW_SEL") (pintype "bidirectional"))
      (node (ref "U$7") (pin "GND") (pinfunction "GND_GND") (pintype "bidirectional"))
      (node (ref "U$8") (pin "BW_SEL") (pinfunction "BW_SEL_BW_SEL") (pintype "bidirectional"))
      (node (ref "U$8") (pin "GND") (pinfunction "GND_GND") (pintype "bidirectional"))
      (node (ref "U$9") (pin "GND") (pinfunction "GND_GND") (pintype "bidirectional"))
      (node (ref "U1") (pin "3") (pinfunction "VIN(-)/GND_3") (pintype "power_in"))
      (node (ref "U1") (pin "4") (pinfunction "VOUT(-)/GND_4") (pintype "power_in"))
      (node (ref "U3") (pin "3") (pinfunction "VIN(-)/GND_3") (pintype "power_in"))
      (node (ref "U3") (pin "4") (pinfunction "VOUT(-)/GND_4") (pintype "power_in"))
    )
    (net (code "9") (name "KILL_SWITCH") (class "Default")
      (node (ref "Q8") (pin "2") (pinfunction "S_2") (pintype "bidirectional"))
      (node (ref "R17") (pin "1") (pinfunction "1_1") (pintype "passive"))
      (node (ref "U$1") (pin "37") (pinfunction "KILL_SWITCH_37") (pintype "output"))
    )
    (net (code "10") (name "LIGHTING_1") (class "Default")
      (node (ref "Q3") (pin "1") (pinfunction "G_1") (pintype "bidirectional"))
      (node (ref "U$1") (pin "33") (pinfunction "SPARE3_33") (pintype "bidirectional"))
    )
    (net (code "11") (name "LIGHTING_2") (class "Default")
      (node (ref "Q2") (pin "1") (pinfunction "G_1") (pintype "bidirectional"))
      (node (ref "U$1") (pin "34") (pinfunction "SPARE4_34") (pintype "bidirectional"))
    )
    (net (code "12") (name "MOTOR_POWER") (class "Default")
      (node (ref "ESC_CONN") (pin "1+") (pinfunction "1+_1+") (pintype "bidirectional"))
      (node (ref "ESC_CONN") (pin "2+") (pinfunction "2+_2+") (pintype "bidirectional"))
      (node (ref "ESC_CONN") (pin "3+") (pinfunction "3+_3+") (pintype "bidirectional"))
      (node (ref "ESC_CONN") (pin "4+") (pinfunction "4+_4+") (pintype "bidirectional"))
      (node (ref "ESC_CONN") (pin "5+") (pinfunction "5+_5+") (pintype "bidirectional"))
      (node (ref "ESC_CONN") (pin "6+") (pinfunction "6+_6+") (pintype "bidirectional"))
      (node (ref "ESC_CONN") (pin "7+") (pinfunction "7+_7+") (pintype "bidirectional"))
      (node (ref "Q5") (pin "3") (pinfunction "D_3") (pintype "passive"))
      (node (ref "Q7") (pin "3") (pinfunction "D_3") (pintype "passive"))
    )
    (net (code "13") (name "Net-(5V-PadA)") (class "Default")
      (node (ref "5V") (pin "A") (pinfunction "A_A") (pintype "passive"))
      (node (ref "R23") (pin "1") (pinfunction "1_1") (pintype "passive"))
    )
    (net (code "14") (name "Net-(12V-PadA)") (class "Default")
      (node (ref "12V") (pin "A") (pinfunction "A_A") (pintype "passive"))
      (node (ref "R22") (pin "1") (pinfunction "1_1") (pintype "passive"))
    )
    (net (code "15") (name "Net-(D1-K_1)") (class "Default")
      (node (ref "D1") (pin "1") (pinfunction "K_1_1") (pintype "bidirectional"))
      (node (ref "U$5") (pin "4") (pinfunction "IN_4") (pintype "bidirectional"))
      (node (ref "U$7") (pin "IP-1") (pinfunction "IP-1_IP-1") (pintype "bidirectional"))
      (node (ref "U$7") (pin "IP-2") (pinfunction "IP-2_IP-2") (pintype "bidirectional"))
    )
    (net (code "16") (name "Net-(D1-K_2)") (class "Default")
      (node (ref "D1") (pin "2") (pinfunction "K_2_2") (pintype "bidirectional"))
      (node (ref "U$5") (pin "5") (pinfunction "GATE_5") (pintype "bidirectional"))
    )
    (net (code "17") (name "Net-(D2-K_1)") (class "Default")
      (node (ref "D2") (pin "1") (pinfunction "K_1_1") (pintype "bidirectional"))
      (node (ref "U$6") (pin "4") (pinfunction "IN_4") (pintype "bidirectional"))
      (node (ref "U$8") (pin "IP-1") (pinfunction "IP-1_IP-1") (pintype "bidirectional"))
      (node (ref "U$8") (pin "IP-2") (pinfunction "IP-2_IP-2") (pintype "bidirectional"))
    )
    (net (code "18") (name "Net-(D2-K_2)") (class "Default")
      (node (ref "D2") (pin "2") (pinfunction "K_2_2") (pintype "bidirectional"))
      (node (ref "U$6") (pin "5") (pinfunction "GATE_5") (pintype "bidirectional"))
    )
    (net (code "19") (name "Net-(FAULT_LED-PadA)") (class "Default")
      (node (ref "FAULT_LED") (pin "A") (pinfunction "A_A") (pintype "passive"))
      (node (ref "R16") (pin "1") (pinfunction "1_1") (pintype "passive"))
    )
    (net (code "20") (name "Net-(IC4-1B)") (class "Default")
      (node (ref "IC4") (pin "2") (pinfunction "1B_2") (pintype "input"))
      (node (ref "R39") (pin "2") (pinfunction "2_2") (pintype "passive"))
      (node (ref "R40") (pin "2") (pinfunction "2_2") (pintype "passive"))
    )
    (net (code "21") (name "Net-(IC4-1C)") (class "Default")
      (node (ref "IC4") (pin "13") (pinfunction "1C_13") (pintype "input"))
      (node (ref "R45") (pin "2") (pinfunction "2_2") (pintype "passive"))
      (node (ref "R46") (pin "1") (pinfunction "1_1") (pintype "passive"))
    )
    (net (code "22") (name "Net-(IC4-1Y)") (class "Default")
      (node (ref "IC4") (pin "10") (pinfunction "3B_10") (pintype "input"))
      (node (ref "IC4") (pin "11") (pinfunction "3C_11") (pintype "input"))
      (node (ref "IC4") (pin "12") (pinfunction "1Y_12") (pintype "output"))
    )
    (net (code "23") (name "Net-(IC4-2A)") (class "Default")
      (node (ref "IC4") (pin "3") (pinfunction "2A_3") (pintype "input"))
      (node (ref "R41") (pin "2") (pinfunction "2_2") (pintype "passive"))
      (node (ref "R42") (pin "2") (pinfunction "2_2") (pintype "passive"))
    )
    (net (code "24") (name "Net-(IC4-2B)") (class "Default")
      (node (ref "IC4") (pin "4") (pinfunction "2B_4") (pintype "input"))
      (node (ref "R43") (pin "2") (pinfunction "2_2") (pintype "passive"))
      (node (ref "R44") (pin "2") (pinfunction "2_2") (pintype "passive"))
    )
    (net (code "25") (name "Net-(IC4-2C)") (class "Default")
      (node (ref "IC4") (pin "5") (pinfunction "2C_5") (pintype "input"))
      (node (ref "R47") (pin "2") (pinfunction "2_2") (pintype "passive"))
      (node (ref "R48") (pin "2") (pinfunction "2_2") (pintype "passive"))
    )
    (net (code "26") (name "Net-(IC4-2Y)") (class "Default")
      (node (ref "IC4") (pin "6") (pinfunction "2Y_6") (pintype "output"))
      (node (ref "IC4") (pin "9") (pinfunction "3A_9") (pintype "input"))
    )
    (net (code "27") (name "Net-(KILLSWITCH-PadC)") (class "Default")
      (node (ref "KILLSWITCH") (pin "C") (pinfunction "C_C") (pintype "passive"))
      (node (ref "R17") (pin "2") (pinfunction "2_2") (pintype "passive"))
    )
    (net (code "28") (name "Net-(PORT-PadA)") (class "Default")
      (node (ref "PORT") (pin "A") (pinfunction "A_A") (pintype "passive"))
      (node (ref "R19") (pin "1") (pinfunction "1_1") (pintype "passive"))
    )
    (net (code "29") (name "Net-(Q1-G)") (class "Default")
      (node (ref "Q1") (pin "1") (pinfunction "G_1") (pintype "passive"))
      (node (ref "R20") (pin "1") (pinfunction "1_1") (pintype "passive"))
      (node (ref "T1") (pin "1") (pinfunction "D_1") (pintype "passive"))
    )
    (net (code "30") (name "Net-(Q2-D)") (class "Default")
      (node (ref "LIGHTING") (pin "4") (pinfunction "4_4") (pintype "passive"))
      (node (ref "Q2") (pin "2") (pinfunction "D_2") (pintype "bidirectional"))
    )
    (net (code "31") (name "Net-(Q3-D)") (class "Default")
      (node (ref "LIGHTING") (pin "3") (pinfunction "3_3") (pintype "passive"))
      (node (ref "Q3") (pin "2") (pinfunction "D_2") (pintype "bidirectional"))
    )
    (net (code "32") (name "Net-(Q4-G)") (class "Default")
      (node (ref "C1") (pin "2") (pinfunction "2_2") (pintype "passive"))
      (node (ref "Q4") (pin "1") (pinfunction "G_1") (pintype "passive"))
      (node (ref "R24") (pin "2") (pinfunction "2_2") (pintype "passive"))
      (node (ref "R25") (pin "1") (pinfunction "1_1") (pintype "passive"))
    )
    (net (code "33") (name "Net-(Q5-G)") (class "Default")
      (node (ref "Q5") (pin "1") (pinfunction "G_1") (pintype "passive"))
      (node (ref "Q7") (pin "1") (pinfunction "G_1") (pintype "passive"))
      (node (ref "R18") (pin "1") (pinfunction "1_1") (pintype "passive"))
      (node (ref "R4") (pin "2") (pinfunction "2_2") (pintype "passive"))
    )
    (net (code "34") (name "Net-(Q6-D)") (class "Default")
      (node (ref "Q6") (pin "3") (pinfunction "D_3") (pintype "bidirectional"))
      (node (ref "U3") (pin "2") (pinfunction "ON/OFF_2") (pintype "input"))
    )
    (net (code "35") (name "Net-(Q8-D)") (class "Default")
      (node (ref "Q8") (pin "3") (pinfunction "D_3") (pintype "bidirectional"))
      (node (ref "R4") (pin "1") (pinfunction "1_1") (pintype "passive"))
    )
    (net (code "36") (name "Net-(Q9-D)") (class "Default")
      (node (ref "Q9") (pin "3") (pinfunction "D_3") (pintype "bidirectional"))
      (node (ref "U1") (pin "2") (pinfunction "ON/OFF_2") (pintype "input"))
    )
    (net (code "37") (name "Net-(R1-A)") (class "Default")
      (node (ref "R1") (pin "1") (pinfunction "A_1") (pintype "passive"))
      (node (ref "U3") (pin "6") (pinfunction "TRIM_6") (pintype "passive"))
    )
    (net (code "38") (name "Net-(R5-Pad1)") (class "Default")
      (node (ref "R5") (pin "1") (pinfunction "1_1") (pintype "passive"))
      (node (ref "R8") (pin "1") (pinfunction "1_1") (pintype "passive"))
      (node (ref "U$9") (pin "IN4") (pinfunction "IN4_IN4") (pintype "bidirectional"))
    )
    (net (code "39") (name "Net-(R6-Pad1)") (class "Default")
      (node (ref "R6") (pin "1") (pinfunction "1_1") (pintype "passive"))
      (node (ref "R9") (pin "1") (pinfunction "1_1") (pintype "passive"))
      (node (ref "U$9") (pin "IN3") (pinfunction "IN3_IN3") (pintype "bidirectional"))
    )
    (net (code "40") (name "Net-(R10-Pad1)") (class "Default")
      (node (ref "R10") (pin "1") (pinfunction "1_1") (pintype "passive"))
      (node (ref "R7") (pin "1") (pinfunction "1_1") (pintype "passive"))
      (node (ref "U$9") (pin "IN2") (pinfunction "IN2_IN2") (pintype "bidirectional"))
    )
    (net (code "41") (name "Net-(R11-Pad1)") (class "Default")
      (node (ref "R11") (pin "1") (pinfunction "1_1") (pintype "passive"))
      (node (ref "R14") (pin "1") (pinfunction "1_1") (pintype "passive"))
      (node (ref "U$9") (pin "IN5") (pinfunction "IN5_IN5") (pintype "bidirectional"))
    )
    (net (code "42") (name "Net-(R12-Pad2)") (class "Default")
      (node (ref "R12") (pin "2") (pinfunction "2_2") (pintype "passive"))
      (node (ref "R13") (pin "2") (pinfunction "2_2") (pintype "passive"))
      (node (ref "U$9") (pin "A1") (pinfunction "A1_A1") (pintype "bidirectional"))
    )
    (net (code "43") (name "Net-(R15-Pad1)") (class "Default")
      (node (ref "R15") (pin "1") (pinfunction "1_1") (pintype "passive"))
      (node (ref "R26") (pin "1") (pinfunction "1_1") (pintype "passive"))
      (node (ref "U$9") (pin "IN6") (pinfunction "IN6_IN6") (pintype "bidirectional"))
    )
    (net (code "44") (name "Net-(R21-Pad1)") (class "Default")
      (node (ref "R21") (pin "1") (pinfunction "1_1") (pintype "passive"))
      (node (ref "STBD") (pin "A") (pinfunction "A_A") (pintype "passive"))
    )
    (net (code "45") (name "Net-(R28-A)") (class "Default")
      (node (ref "R28") (pin "1") (pinfunction "A_1") (pintype "passive"))
      (node (ref "U1") (pin "6") (pinfunction "TRIM_6") (pintype "passive"))
    )
    (net (code "46") (name "Net-(T3-D)") (class "Default")
      (node (ref "R24") (pin "1") (pinfunction "1_1") (pintype "passive"))
      (node (ref "T3") (pin "1") (pinfunction "D_1") (pintype "passive"))
    )
    (net (code "47") (name "Net-(U1-VIN(+))") (class "Default")
      (node (ref "C13") (pin "+") (pinfunction "+_+") (pintype "passive"))
      (node (ref "L3") (pin "2") (pinfunction "2_2") (pintype "passive"))
      (node (ref "U1") (pin "1") (pinfunction "VIN(+)_1") (pintype "input"))
    )
    (net (code "48") (name "Net-(U3-VIN(+))") (class "Default")
      (node (ref "C12") (pin "+") (pinfunction "+_+") (pintype "passive"))
      (node (ref "L2") (pin "2") (pinfunction "2_2") (pintype "passive"))
      (node (ref "U3") (pin "1") (pinfunction "VIN(+)_1") (pintype "input"))
    )
    (net (code "49") (name "PLTA_ALT") (class "Default")
      (node (ref "MYNT_XAVIER_PLTA") (pin "8") (pinfunction "8_8") (pintype "passive"))
      (node (ref "Q1") (pin "3") (pinfunction "D_3") (pintype "passive"))
    )
    (net (code "50") (name "PLTA_SWITCH") (class "Default")
      (node (ref "T1") (pin "3") (pinfunction "G_3") (pintype "passive"))
      (node (ref "U$1") (pin "50") (pinfunction "SPARE8_50") (pintype "bidirectional"))
    )
    (net (code "51") (name "PORT_BAT") (class "Default")
      (node (ref "BATTERYCONNECTOR") (pin "13") (pinfunction "13_13") (pintype "passive"))
      (node (ref "BATTERYCONNECTOR") (pin "14") (pinfunction "14_14") (pintype "passive"))
      (node (ref "BATTERYCONNECTOR") (pin "15") (pinfunction "15_15") (pintype "passive"))
      (node (ref "BATTERYCONNECTOR") (pin "16") (pinfunction "16_16") (pintype "passive"))
      (node (ref "PORT") (pin "C") (pinfunction "C_C") (pintype "passive"))
      (node (ref "R41") (pin "1") (pinfunction "1_1") (pintype "passive"))
      (node (ref "R5") (pin "2") (pinfunction "2_2") (pintype "passive"))
      (node (ref "U$7") (pin "IP+1") (pinfunction "IP+1_IP+1") (pintype "bidirectional"))
      (node (ref "U$7") (pin "IP+2") (pinfunction "IP+2_IP+2") (pintype "bidirectional"))
    )
    (net (code "52") (name "PORT_CURRENT") (class "Default")
      (node (ref "U$7") (pin "VIOUT") (pinfunction "VIOUT_VIOUT") (pintype "bidirectional"))
      (node (ref "U$9") (pin "IN1") (pinfunction "IN1_IN1") (pintype "bidirectional"))
    )
    (net (code "53") (name "SENSOR_SCL") (class "Default")
      (node (ref "U$1") (pin "29") (pinfunction "SENSOR_SCL_29") (pintype "bidirectional"))
      (node (ref "U$9") (pin "SCL") (pinfunction "SCL_SCL") (pintype "bidirectional"))
    )
    (net (code "54") (name "SENSOR_SDA") (class "Default")
      (node (ref "U$1") (pin "30") (pinfunction "SENSOR_SDA_30") (pintype "bidirectional"))
      (node (ref "U$9") (pin "SDA") (pinfunction "SDA_SDA") (pintype "bidirectional"))
    )
    (net (code "55") (name "STBD_BAT") (class "Default")
      (node (ref "BATTERYCONNECTOR") (pin "10") (pinfunction "10_10") (pintype "passive"))
      (node (ref "BATTERYCONNECTOR") (pin "11") (pinfunction "11_11") (pintype "passive"))
      (node (ref "BATTERYCONNECTOR") (pin "12") (pinfunction "12_12") (pintype "passive"))
      (node (ref "BATTERYCONNECTOR") (pin "9") (pinfunction "9_9") (pintype "passive"))
      (node (ref "R44") (pin "1") (pinfunction "1_1") (pintype "passive"))
      (node (ref "R6") (pin "2") (pinfunction "2_2") (pintype "passive"))
      (node (ref "STBD") (pin "C") (pinfunction "C_C") (pintype "passive"))
      (node (ref "U$8") (pin "IP+1") (pinfunction "IP+1_IP+1") (pintype "bidirectional"))
      (node (ref "U$8") (pin "IP+2") (pinfunction "IP+2_IP+2") (pintype "bidirectional"))
    )
    (net (code "56") (name "STBD_CURRENT") (class "Default")
      (node (ref "U$8") (pin "VIOUT") (pinfunction "VIOUT_VIOUT") (pintype "bidirectional"))
      (node (ref "U$9") (pin "IN0") (pinfunction "IN0_IN0") (pintype "bidirectional"))
    )
    (net (code "57") (name "V+") (class "Default")
      (node (ref "ACTUATOR") (pin "3") (pinfunction "3_3") (pintype "passive"))
      (node (ref "D1") (pin "3") (pinfunction "A_3") (pintype "bidirectional"))
      (node (ref "D2") (pin "3") (pinfunction "A_3") (pintype "bidirectional"))
      (node (ref "L2") (pin "1") (pinfunction "1_1") (pintype "passive"))
      (node (ref "L3") (pin "1") (pinfunction "1_1") (pintype "passive"))
      (node (ref "Q5") (pin "2") (pinfunction "S_2") (pintype "passive"))
      (node (ref "Q7") (pin "2") (pinfunction "S_2") (pintype "passive"))
      (node (ref "R18") (pin "2") (pinfunction "2_2") (pintype "passive"))
      (node (ref "R2") (pin "1") (pinfunction "1_1") (pintype "passive"))
      (node (ref "R32") (pin "1") (pinfunction "1_1") (pintype "passive"))
      (node (ref "R48") (pin "1") (pinfunction "1_1") (pintype "passive"))
      (node (ref "R7") (pin "2") (pinfunction "2_2") (pintype "passive"))
      (node (ref "U$5") (pin "1") (pinfunction "VS_1") (pintype "bidirectional"))
      (node (ref "U$5") (pin "6") (pinfunction "OUT_6") (pintype "bidirectional"))
      (node (ref "U$6") (pin "1") (pinfunction "VS_1") (pintype "bidirectional"))
      (node (ref "U$6") (pin "6") (pinfunction "OUT_6") (pintype "bidirectional"))
    )
    (net (code "58") (name "XAVIER_ALT") (class "Default")
      (node (ref "MYNT_XAVIER_PLTA") (pin "5") (pinfunction "5_5") (pintype "passive"))
      (node (ref "Q4") (pin "3") (pinfunction "D_3") (pintype "passive"))
    )
    (net (code "59") (name "XAVIER_SWITCH") (class "Default")
      (node (ref "T3") (pin "3") (pinfunction "G_3") (pintype "passive"))
      (node (ref "U$1") (pin "19") (pinfunction "MOBO_ON/OFF_19") (pintype "bidirectional"))
    )
    (net (code "60") (name "unconnected-(R1-E-Pad3)") (class "Default")
      (node (ref "R1") (pin "3") (pinfunction "E_3") (pintype "passive"))
    )
    (net (code "61") (name "unconnected-(R28-E-Pad3)") (class "Default")
      (node (ref "R28") (pin "3") (pinfunction "E_3") (pintype "passive"))
    )
    (net (code "62") (name "unconnected-(U$1-ACOUSTIC_ON{slash}OFF-Pad17)") (class "Default")
      (node (ref "U$1") (pin "17") (pinfunction "ACOUSTIC_ON/OFF_17") (pintype "bidirectional"))
    )
    (net (code "63") (name "unconnected-(U$1-BOARD_SCL-Pad31)") (class "Default")
      (node (ref "U$1") (pin "31") (pinfunction "BOARD_SCL_31") (pintype "bidirectional"))
    )
    (net (code "64") (name "unconnected-(U$1-BOARD_SDA-Pad32)") (class "Default")
      (node (ref "U$1") (pin "32") (pinfunction "BOARD_SDA_32") (pintype "bidirectional"))
    )
    (net (code "65") (name "unconnected-(U$1-JETSON_ON{slash}OFF-Pad18)") (class "Default")
      (node (ref "U$1") (pin "18") (pinfunction "JETSON_ON/OFF_18") (pintype "bidirectional"))
    )
    (net (code "66") (name "unconnected-(U$1-PWM_1-Pad20)") (class "Default")
      (node (ref "U$1") (pin "20") (pinfunction "PWM_1_20") (pintype "bidirectional"))
    )
    (net (code "67") (name "unconnected-(U$1-PWM_2-Pad21)") (class "Default")
      (node (ref "U$1") (pin "21") (pinfunction "PWM_2_21") (pintype "bidirectional"))
    )
    (net (code "68") (name "unconnected-(U$1-PWM_3-Pad22)") (class "Default")
      (node (ref "U$1") (pin "22") (pinfunction "PWM_3_22") (pintype "bidirectional"))
    )
    (net (code "69") (name "unconnected-(U$1-PWM_4-Pad23)") (class "Default")
      (node (ref "U$1") (pin "23") (pinfunction "PWM_4_23") (pintype "bidirectional"))
    )
    (net (code "70") (name "unconnected-(U$1-PWM_5-Pad24)") (class "Default")
      (node (ref "U$1") (pin "24") (pinfunction "PWM_5_24") (pintype "bidirectional"))
    )
    (net (code "71") (name "unconnected-(U$1-PWM_6-Pad25)") (class "Default")
      (node (ref "U$1") (pin "25") (pinfunction "PWM_6_25") (pintype "bidirectional"))
    )
    (net (code "72") (name "unconnected-(U$1-PWM_7-Pad26)") (class "Default")
      (node (ref "U$1") (pin "26") (pinfunction "PWM_7_26") (pintype "bidirectional"))
    )
    (net (code "73") (name "unconnected-(U$1-PWM_8-Pad27)") (class "Default")
      (node (ref "U$1") (pin "27") (pinfunction "PWM_8_27") (pintype "bidirectional"))
    )
    (net (code "74") (name "unconnected-(U$1-SPARE1-Pad7)") (class "Default")
      (node (ref "U$1") (pin "7") (pinfunction "SPARE1_7") (pintype "bidirectional"))
    )
    (net (code "75") (name "unconnected-(U$1-SPARE2-Pad28)") (class "Default")
      (node (ref "U$1") (pin "28") (pinfunction "SPARE2_28") (pintype "bidirectional"))
    )
    (net (code "76") (name "unconnected-(U$1-SPARE5-Pad35)") (class "Default")
      (node (ref "U$1") (pin "35") (pinfunction "SPARE5_35") (pintype "bidirectional"))
    )
    (net (code "77") (name "unconnected-(U$1-SPARE6-Pad36)") (class "Default")
      (node (ref "U$1") (pin "36") (pinfunction "SPARE6_36") (pintype "bidirectional"))
    )
    (net (code "78") (name "unconnected-(U$1-SWITCH_1-Pad38)") (class "Default")
      (node (ref "U$1") (pin "38") (pinfunction "SWITCH_1_38") (pintype "output"))
    )
    (net (code "79") (name "unconnected-(U$1-SWITCH_2-Pad39)") (class "Default")
      (node (ref "U$1") (pin "39") (pinfunction "SWITCH_2_39") (pintype "output"))
    )
    (net (code "80") (name "unconnected-(U$1-SWITCH_3-Pad40)") (class "Default")
      (node (ref "U$1") (pin "40") (pinfunction "SWITCH_3_40") (pintype "output"))
    )
    (net (code "81") (name "unconnected-(U$1-SWITCH_4-Pad41)") (class "Default")
      (node (ref "U$1") (pin "41") (pinfunction "SWITCH_4_41") (pintype "output"))
    )
    (net (code "82") (name "unconnected-(U$1-SWITCH_5-Pad42)") (class "Default")
      (node (ref "U$1") (pin "42") (pinfunction "SWITCH_5_42") (pintype "output"))
    )
    (net (code "83") (name "unconnected-(U$5-OFF-Pad3)") (class "Default")
      (node (ref "U$5") (pin "3") (pinfunction "OFF_3") (pintype "bidirectional"))
    )
    (net (code "84") (name "unconnected-(U$6-OFF-Pad3)") (class "Default")
      (node (ref "U$6") (pin "3") (pinfunction "OFF_3") (pintype "bidirectional"))
    )
    (net (code "85") (name "unconnected-(U$9-PadIN7)") (class "Default")
      (node (ref "U$9") (pin "IN7") (pinfunction "IN7_IN7") (pintype "bidirectional"))
    )
    (net (code "86") (name "unconnected-(U$9-PadINT)") (class "Default")
      (node (ref "U$9") (pin "INT") (pinfunction "INT_INT") (pintype "bidirectional"))
    )
    (net (code "87") (name "unconnected-(U$9-PadV+)") (class "Default")
      (node (ref "U$9") (pin "V+") (pinfunction "V+_V+") (pintype "bidirectional"))
    )
  )
)
